# SCHEMATICS.net
KiCad netlist of a schematic drawn in Altium Designer
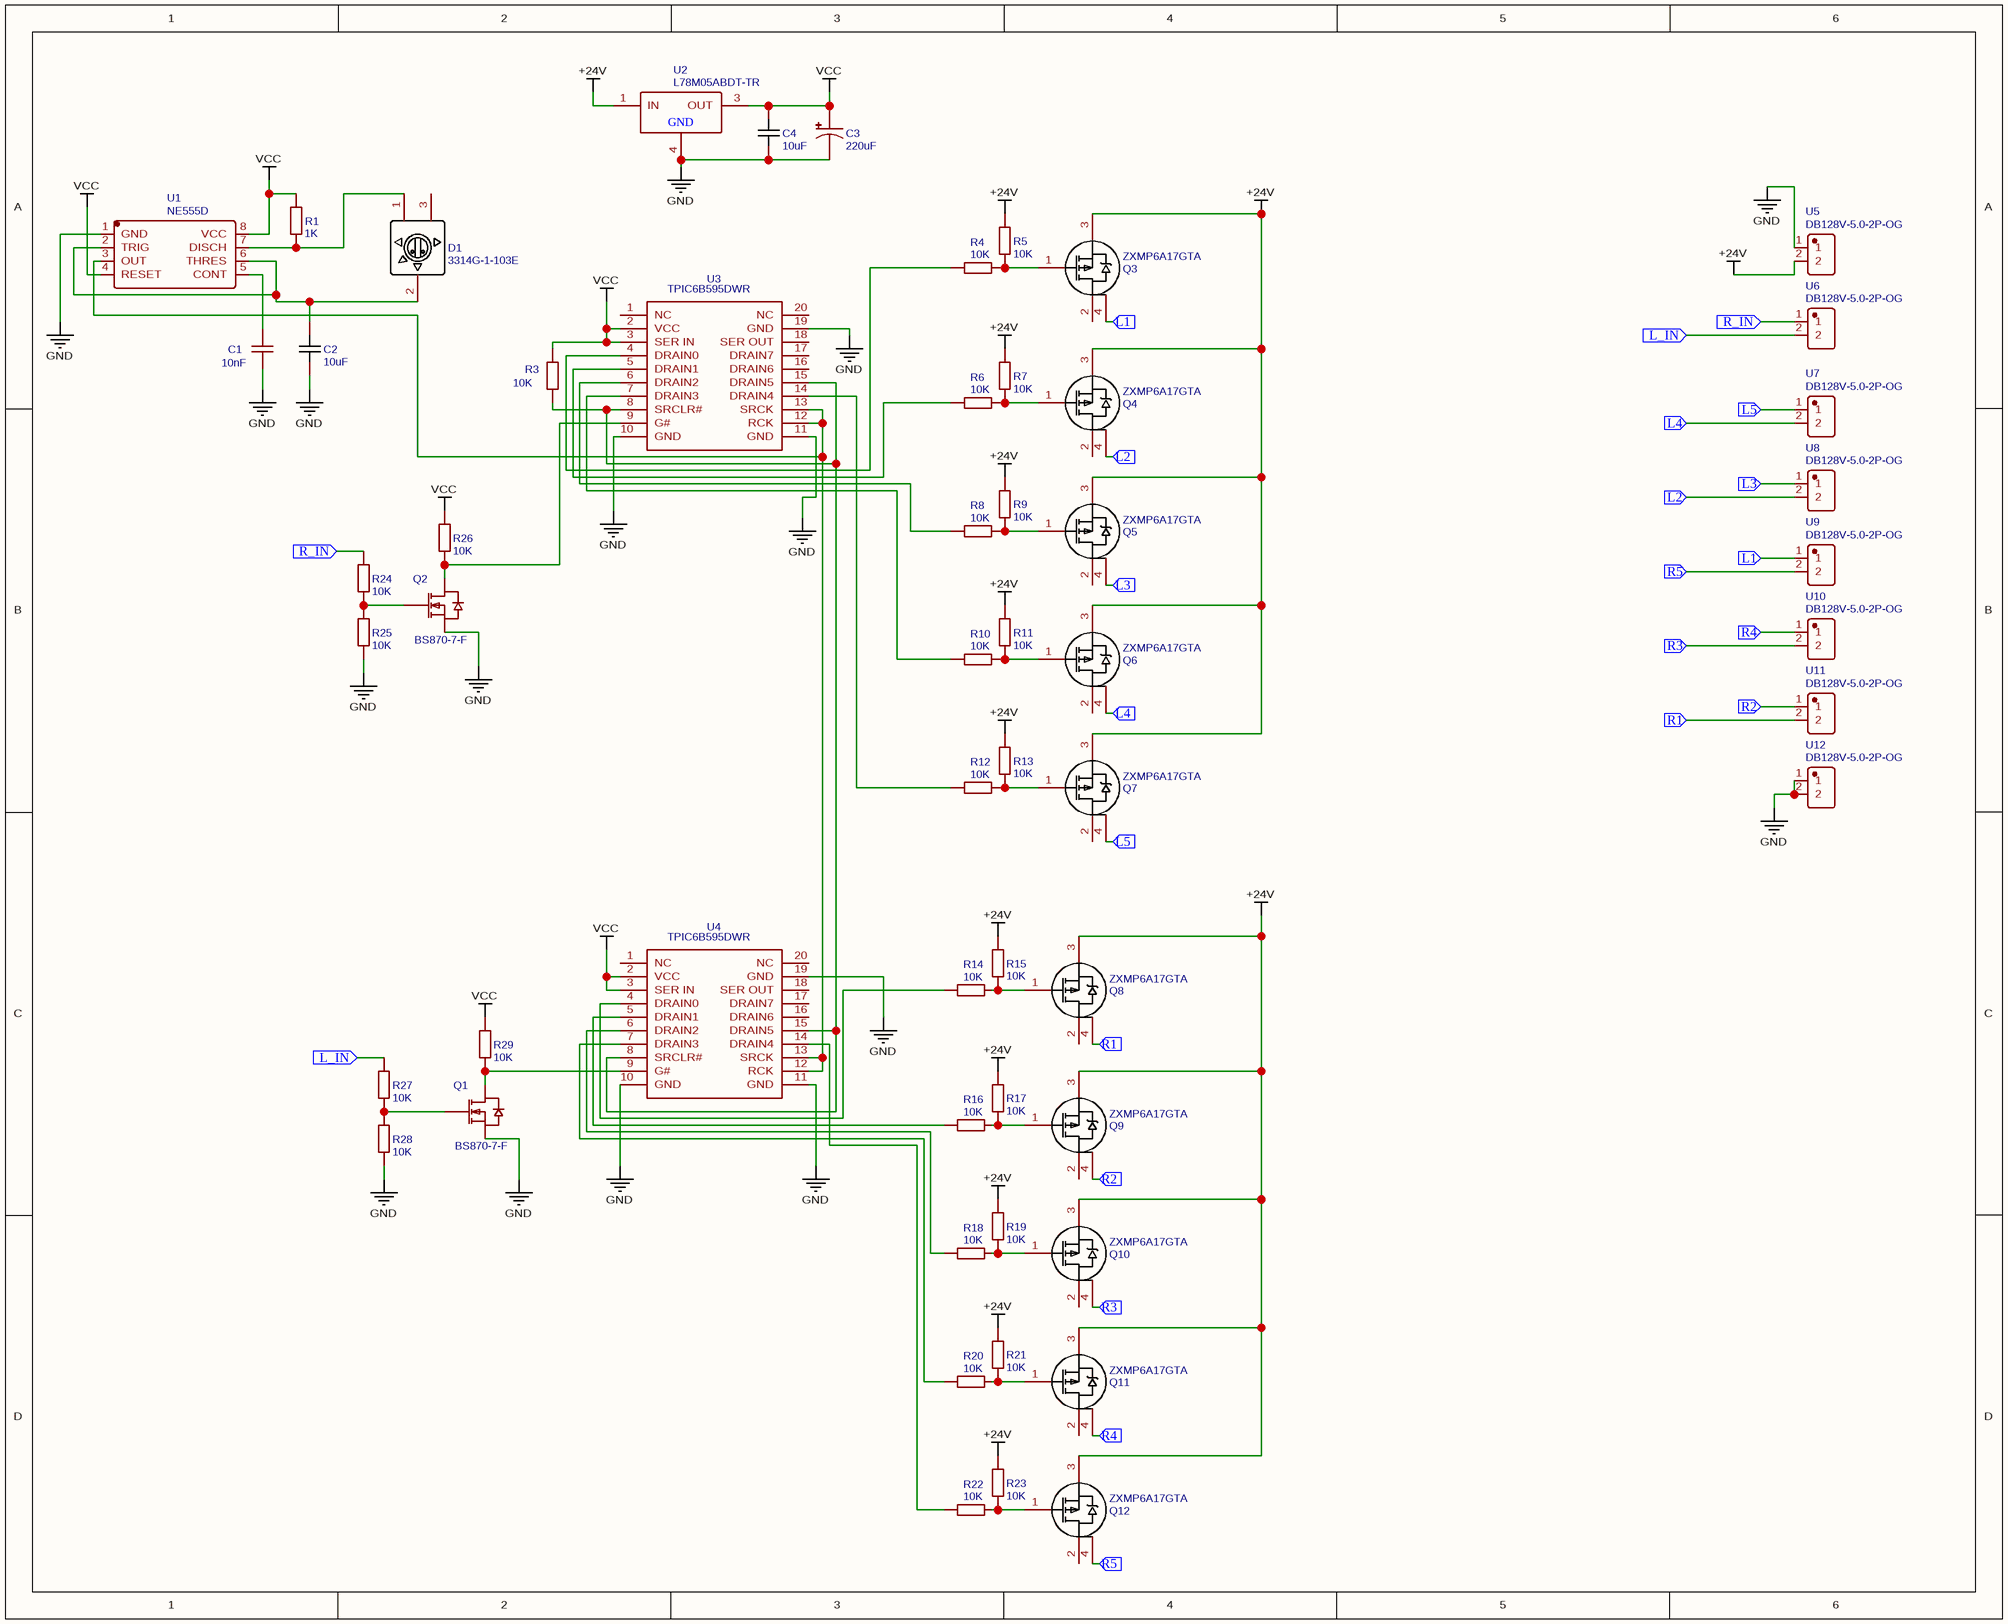
[diagram p0: SCHEMATICS.schdoc]

(export (version "E")
  (design (tool "Eeschema 10.0.6"))
  (components
    (comp (ref "C1")
      (value "10nF")
      (fields
        (field (name "BOM_MANUFACTURER PART") "CL10B103KC8NNNC")
        (field (name "BOM_SUPPLIER PART") "C84709")
        (field (name "CONTRIBUTOR") "LCSC")
      )
      (libsource (lib "altium-import") (part "root_3_10nF_"))
    )
    (comp (ref "C2")
      (value "10uF")
      (fields
        (field (name "BOM_MANUFACTURER PART") "CL10A106KP8NNNC")
        (field (name "BOM_SUPPLIER PART") "C19702")
      )
      (libsource (lib "altium-import") (part "root_3_10uF_"))
    )
    (comp (ref "C3")
      (value "220uF")
      (fields
        (field (name "BOM_SUPPLIER PART") "C250080")
        (field (name "BOM_MANUFACTURER PART") "OVU221M1C1010-TRO")
        (field (name "CONTRIBUTOR") "LCSC")
      )
      (libsource (lib "altium-import") (part "root_0_220uF_"))
    )
    (comp (ref "C4")
      (value "10uF")
      (fields
        (field (name "BOM_MANUFACTURER PART") "CL10A106KP8NNNC")
        (field (name "BOM_SUPPLIER PART") "C19702")
      )
      (libsource (lib "altium-import") (part "root_3_10uF_"))
    )
    (comp (ref "D1")
      (value "3314G-1-103E")
      (fields (field (name "BOM_SUPPLIER PART") "C780220") (field (name "CONTRIBUTOR") "LCSC"))
      (libsource (lib "altium-import") (part "root_2_3314G-1-103E_"))
    )
    (comp (ref "Q1")
      (value "BS870-7-F")
      (fields (field (name "BOM_SUPPLIER PART") "C216212") (field (name "CONTRIBUTOR") "LCSC"))
      (libsource (lib "altium-import") (part "root_0_BS870-7-F_"))
    )
    (comp (ref "Q2")
      (value "BS870-7-F")
      (fields (field (name "BOM_SUPPLIER PART") "C216212") (field (name "CONTRIBUTOR") "LCSC"))
      (libsource (lib "altium-import") (part "root_0_BS870-7-F_"))
    )
    (comp (ref "Q3")
      (value "ZXMP6A17GTA")
      (fields (field (name "BOM_SUPPLIER PART") "C154719") (field (name "CONTRIBUTOR") "LCSC"))
      (libsource (lib "altium-import") (part "root_0_ZXMP6A17GTA_"))
    )
    (comp (ref "Q4")
      (value "ZXMP6A17GTA")
      (fields (field (name "BOM_SUPPLIER PART") "C154719") (field (name "CONTRIBUTOR") "LCSC"))
      (libsource (lib "altium-import") (part "root_0_ZXMP6A17GTA_"))
    )
    (comp (ref "Q5")
      (value "ZXMP6A17GTA")
      (fields (field (name "BOM_SUPPLIER PART") "C154719") (field (name "CONTRIBUTOR") "LCSC"))
      (libsource (lib "altium-import") (part "root_0_ZXMP6A17GTA_"))
    )
    (comp (ref "Q6")
      (value "ZXMP6A17GTA")
      (fields (field (name "BOM_SUPPLIER PART") "C154719") (field (name "CONTRIBUTOR") "LCSC"))
      (libsource (lib "altium-import") (part "root_0_ZXMP6A17GTA_"))
    )
    (comp (ref "Q7")
      (value "ZXMP6A17GTA")
      (fields (field (name "BOM_SUPPLIER PART") "C154719") (field (name "CONTRIBUTOR") "LCSC"))
      (libsource (lib "altium-import") (part "root_0_ZXMP6A17GTA_"))
    )
    (comp (ref "Q8")
      (value "ZXMP6A17GTA")
      (fields (field (name "BOM_SUPPLIER PART") "C154719") (field (name "CONTRIBUTOR") "LCSC"))
      (libsource (lib "altium-import") (part "root_0_ZXMP6A17GTA_"))
    )
    (comp (ref "Q9")
      (value "ZXMP6A17GTA")
      (fields (field (name "BOM_SUPPLIER PART") "C154719") (field (name "CONTRIBUTOR") "LCSC"))
      (libsource (lib "altium-import") (part "root_0_ZXMP6A17GTA_"))
    )
    (comp (ref "Q10")
      (value "ZXMP6A17GTA")
      (fields (field (name "BOM_SUPPLIER PART") "C154719") (field (name "CONTRIBUTOR") "LCSC"))
      (libsource (lib "altium-import") (part "root_0_ZXMP6A17GTA_"))
    )
    (comp (ref "Q11")
      (value "ZXMP6A17GTA")
      (fields (field (name "BOM_SUPPLIER PART") "C154719") (field (name "CONTRIBUTOR") "LCSC"))
      (libsource (lib "altium-import") (part "root_0_ZXMP6A17GTA_"))
    )
    (comp (ref "Q12")
      (value "ZXMP6A17GTA")
      (fields (field (name "BOM_SUPPLIER PART") "C154719") (field (name "CONTRIBUTOR") "LCSC"))
      (libsource (lib "altium-import") (part "root_0_ZXMP6A17GTA_"))
    )
    (comp (ref "R1")
      (value "1K")
      (fields
        (field (name "BOM_MANUFACTURER PART") "0603WAF1001T5E")
        (field (name "BOM_SUPPLIER PART") "C21190")
      )
      (libsource (lib "altium-import") (part "root_3_1K_"))
    )
    (comp (ref "R3")
      (value "10K")
      (fields
        (field (name "BOM_MANUFACTURER PART") "0603WAF1002T5E")
        (field (name "BOM_SUPPLIER PART") "C25804")
      )
      (libsource (lib "altium-import") (part "root_3_10K_"))
    )
    (comp (ref "R4")
      (value "10K")
      (fields
        (field (name "BOM_MANUFACTURER PART") "0603WAF1002T5E")
        (field (name "BOM_SUPPLIER PART") "C25804")
      )
      (libsource (lib "altium-import") (part "root_0_10K_"))
    )
    (comp (ref "R5")
      (value "10K")
      (fields
        (field (name "BOM_MANUFACTURER PART") "0603WAF1002T5E")
        (field (name "BOM_SUPPLIER PART") "C25804")
      )
      (libsource (lib "altium-import") (part "root_3_10K_"))
    )
    (comp (ref "R6")
      (value "10K")
      (fields
        (field (name "BOM_MANUFACTURER PART") "0603WAF1002T5E")
        (field (name "BOM_SUPPLIER PART") "C25804")
      )
      (libsource (lib "altium-import") (part "root_0_10K_"))
    )
    (comp (ref "R7")
      (value "10K")
      (fields
        (field (name "BOM_MANUFACTURER PART") "0603WAF1002T5E")
        (field (name "BOM_SUPPLIER PART") "C25804")
      )
      (libsource (lib "altium-import") (part "root_3_10K_"))
    )
    (comp (ref "R8")
      (value "10K")
      (fields
        (field (name "BOM_MANUFACTURER PART") "0603WAF1002T5E")
        (field (name "BOM_SUPPLIER PART") "C25804")
      )
      (libsource (lib "altium-import") (part "root_0_10K_"))
    )
    (comp (ref "R9")
      (value "10K")
      (fields
        (field (name "BOM_MANUFACTURER PART") "0603WAF1002T5E")
        (field (name "BOM_SUPPLIER PART") "C25804")
      )
      (libsource (lib "altium-import") (part "root_3_10K_"))
    )
    (comp (ref "R10")
      (value "10K")
      (fields
        (field (name "BOM_MANUFACTURER PART") "0603WAF1002T5E")
        (field (name "BOM_SUPPLIER PART") "C25804")
      )
      (libsource (lib "altium-import") (part "root_0_10K_"))
    )
    (comp (ref "R11")
      (value "10K")
      (fields
        (field (name "BOM_MANUFACTURER PART") "0603WAF1002T5E")
        (field (name "BOM_SUPPLIER PART") "C25804")
      )
      (libsource (lib "altium-import") (part "root_3_10K_"))
    )
    (comp (ref "R12")
      (value "10K")
      (fields
        (field (name "BOM_MANUFACTURER PART") "0603WAF1002T5E")
        (field (name "BOM_SUPPLIER PART") "C25804")
      )
      (libsource (lib "altium-import") (part "root_0_10K_"))
    )
    (comp (ref "R13")
      (value "10K")
      (fields
        (field (name "BOM_MANUFACTURER PART") "0603WAF1002T5E")
        (field (name "BOM_SUPPLIER PART") "C25804")
      )
      (libsource (lib "altium-import") (part "root_3_10K_"))
    )
    (comp (ref "R14")
      (value "10K")
      (fields
        (field (name "BOM_MANUFACTURER PART") "0603WAF1002T5E")
        (field (name "BOM_SUPPLIER PART") "C25804")
      )
      (libsource (lib "altium-import") (part "root_0_10K_"))
    )
    (comp (ref "R15")
      (value "10K")
      (fields
        (field (name "BOM_MANUFACTURER PART") "0603WAF1002T5E")
        (field (name "BOM_SUPPLIER PART") "C25804")
      )
      (libsource (lib "altium-import") (part "root_3_10K_"))
    )
    (comp (ref "R16")
      (value "10K")
      (fields
        (field (name "BOM_MANUFACTURER PART") "0603WAF1002T5E")
        (field (name "BOM_SUPPLIER PART") "C25804")
      )
      (libsource (lib "altium-import") (part "root_0_10K_"))
    )
    (comp (ref "R17")
      (value "10K")
      (fields
        (field (name "BOM_MANUFACTURER PART") "0603WAF1002T5E")
        (field (name "BOM_SUPPLIER PART") "C25804")
      )
      (libsource (lib "altium-import") (part "root_3_10K_"))
    )
    (comp (ref "R18")
      (value "10K")
      (fields
        (field (name "BOM_MANUFACTURER PART") "0603WAF1002T5E")
        (field (name "BOM_SUPPLIER PART") "C25804")
      )
      (libsource (lib "altium-import") (part "root_0_10K_"))
    )
    (comp (ref "R19")
      (value "10K")
      (fields
        (field (name "BOM_MANUFACTURER PART") "0603WAF1002T5E")
        (field (name "BOM_SUPPLIER PART") "C25804")
      )
      (libsource (lib "altium-import") (part "root_3_10K_"))
    )
    (comp (ref "R20")
      (value "10K")
      (fields
        (field (name "BOM_MANUFACTURER PART") "0603WAF1002T5E")
        (field (name "BOM_SUPPLIER PART") "C25804")
      )
      (libsource (lib "altium-import") (part "root_0_10K_"))
    )
    (comp (ref "R21")
      (value "10K")
      (fields
        (field (name "BOM_MANUFACTURER PART") "0603WAF1002T5E")
        (field (name "BOM_SUPPLIER PART") "C25804")
      )
      (libsource (lib "altium-import") (part "root_3_10K_"))
    )
    (comp (ref "R22")
      (value "10K")
      (fields
        (field (name "BOM_MANUFACTURER PART") "0603WAF1002T5E")
        (field (name "BOM_SUPPLIER PART") "C25804")
      )
      (libsource (lib "altium-import") (part "root_0_10K_"))
    )
    (comp (ref "R23")
      (value "10K")
      (fields
        (field (name "BOM_MANUFACTURER PART") "0603WAF1002T5E")
        (field (name "BOM_SUPPLIER PART") "C25804")
      )
      (libsource (lib "altium-import") (part "root_3_10K_"))
    )
    (comp (ref "R24")
      (value "10K")
      (fields
        (field (name "BOM_MANUFACTURER PART") "0603WAF1002T5E")
        (field (name "BOM_SUPPLIER PART") "C25804")
      )
      (libsource (lib "altium-import") (part "root_1_10K_"))
    )
    (comp (ref "R25")
      (value "10K")
      (fields
        (field (name "BOM_MANUFACTURER PART") "0603WAF1002T5E")
        (field (name "BOM_SUPPLIER PART") "C25804")
      )
      (libsource (lib "altium-import") (part "root_1_10K_"))
    )
    (comp (ref "R26")
      (value "10K")
      (fields
        (field (name "BOM_MANUFACTURER PART") "0603WAF1002T5E")
        (field (name "BOM_SUPPLIER PART") "C25804")
      )
      (libsource (lib "altium-import") (part "root_1_10K_"))
    )
    (comp (ref "R27")
      (value "10K")
      (fields
        (field (name "BOM_MANUFACTURER PART") "0603WAF1002T5E")
        (field (name "BOM_SUPPLIER PART") "C25804")
      )
      (libsource (lib "altium-import") (part "root_1_10K_"))
    )
    (comp (ref "R28")
      (value "10K")
      (fields
        (field (name "BOM_MANUFACTURER PART") "0603WAF1002T5E")
        (field (name "BOM_SUPPLIER PART") "C25804")
      )
      (libsource (lib "altium-import") (part "root_1_10K_"))
    )
    (comp (ref "R29")
      (value "10K")
      (fields
        (field (name "BOM_MANUFACTURER PART") "0603WAF1002T5E")
        (field (name "BOM_SUPPLIER PART") "C25804")
      )
      (libsource (lib "altium-import") (part "root_1_10K_"))
    )
    (comp (ref "U1")
      (value "NE555D")
      (fields (field (name "BOM_SUPPLIER PART") "C234230") (field (name "CONTRIBUTOR") "LCSC"))
      (libsource (lib "altium-import") (part "root_0_NE555D_"))
    )
    (comp (ref "U2")
      (value "L78M05ABDT-TR")
      (fields (field (name "BOM_SUPPLIER PART") "C58069"))
      (libsource (lib "altium-import") (part "root_0_L78M05ABDT-TR_"))
    )
    (comp (ref "U3")
      (value "TPIC6B595DWR")
      (fields (field (name "BOM_SUPPLIER PART") "C7094"))
      (libsource (lib "altium-import") (part "root_0_TPIC6B595DWR_"))
    )
    (comp (ref "U4")
      (value "TPIC6B595DWR")
      (fields (field (name "BOM_SUPPLIER PART") "C7094"))
      (libsource (lib "altium-import") (part "root_0_TPIC6B595DWR_"))
    )
    (comp (ref "U5")
      (value "DB128V-5.0-2P-OG")
      (fields (field (name "BOM_SUPPLIER PART") "C424694") (field (name "CONTRIBUTOR") "LCSC"))
      (libsource (lib "altium-import") (part "root_0_DB128V-5.0-2P-OG_"))
    )
    (comp (ref "U6")
      (value "DB128V-5.0-2P-OG")
      (fields (field (name "BOM_SUPPLIER PART") "C424694") (field (name "CONTRIBUTOR") "LCSC"))
      (libsource (lib "altium-import") (part "root_0_DB128V-5.0-2P-OG_"))
    )
    (comp (ref "U7")
      (value "DB128V-5.0-2P-OG")
      (fields (field (name "BOM_SUPPLIER PART") "C424694") (field (name "CONTRIBUTOR") "LCSC"))
      (libsource (lib "altium-import") (part "root_0_DB128V-5.0-2P-OG_"))
    )
    (comp (ref "U8")
      (value "DB128V-5.0-2P-OG")
      (fields (field (name "BOM_SUPPLIER PART") "C424694") (field (name "CONTRIBUTOR") "LCSC"))
      (libsource (lib "altium-import") (part "root_0_DB128V-5.0-2P-OG_"))
    )
    (comp (ref "U9")
      (value "DB128V-5.0-2P-OG")
      (fields (field (name "BOM_SUPPLIER PART") "C424694") (field (name "CONTRIBUTOR") "LCSC"))
      (libsource (lib "altium-import") (part "root_0_DB128V-5.0-2P-OG_"))
    )
    (comp (ref "U10")
      (value "DB128V-5.0-2P-OG")
      (fields (field (name "BOM_SUPPLIER PART") "C424694") (field (name "CONTRIBUTOR") "LCSC"))
      (libsource (lib "altium-import") (part "root_0_DB128V-5.0-2P-OG_"))
    )
    (comp (ref "U11")
      (value "DB128V-5.0-2P-OG")
      (fields (field (name "BOM_SUPPLIER PART") "C424694") (field (name "CONTRIBUTOR") "LCSC"))
      (libsource (lib "altium-import") (part "root_0_DB128V-5.0-2P-OG_"))
    )
    (comp (ref "U12")
      (value "DB128V-5.0-2P-OG")
      (fields (field (name "BOM_SUPPLIER PART") "C424694") (field (name "CONTRIBUTOR") "LCSC"))
      (libsource (lib "altium-import") (part "root_0_DB128V-5.0-2P-OG_"))
    )
  )
  (nets
    (net (code "1") (name "+24V") (class "Default")
      (node (ref "Q10") (pin "3") (pinfunction "S_3") (pintype "passive"))
      (node (ref "Q11") (pin "3") (pinfunction "S_3") (pintype "passive"))
      (node (ref "Q12") (pin "3") (pinfunction "S_3") (pintype "passive"))
      (node (ref "Q3") (pin "3") (pinfunction "S_3") (pintype "passive"))
      (node (ref "Q4") (pin "3") (pinfunction "S_3") (pintype "passive"))
      (node (ref "Q5") (pin "3") (pinfunction "S_3") (pintype "passive"))
      (node (ref "Q6") (pin "3") (pinfunction "S_3") (pintype "passive"))
      (node (ref "Q7") (pin "3") (pinfunction "S_3") (pintype "passive"))
      (node (ref "Q8") (pin "3") (pinfunction "S_3") (pintype "passive"))
      (node (ref "Q9") (pin "3") (pinfunction "S_3") (pintype "passive"))
      (node (ref "R11") (pin "1") (pinfunction "1_1") (pintype "passive"))
      (node (ref "R13") (pin "1") (pinfunction "1_1") (pintype "passive"))
      (node (ref "R15") (pin "1") (pinfunction "1_1") (pintype "passive"))
      (node (ref "R17") (pin "1") (pinfunction "1_1") (pintype "passive"))
      (node (ref "R19") (pin "1") (pinfunction "1_1") (pintype "passive"))
      (node (ref "R21") (pin "1") (pinfunction "1_1") (pintype "passive"))
      (node (ref "R23") (pin "1") (pinfunction "1_1") (pintype "passive"))
      (node (ref "R5") (pin "1") (pinfunction "1_1") (pintype "passive"))
      (node (ref "R7") (pin "1") (pinfunction "1_1") (pintype "passive"))
      (node (ref "R9") (pin "1") (pinfunction "1_1") (pintype "passive"))
      (node (ref "U2") (pin "1") (pinfunction "IN_1") (pintype "passive"))
      (node (ref "U5") (pin "2") (pinfunction "2_2") (pintype "passive"))
    )
    (net (code "2") (name "/L1") (class "Default")
      (node (ref "Q3") (pin "4") (pinfunction "D_4") (pintype "passive"))
      (node (ref "U9") (pin "1") (pinfunction "1_1") (pintype "passive"))
    )
    (net (code "3") (name "/L2") (class "Default")
      (node (ref "Q4") (pin "4") (pinfunction "D_4") (pintype "passive"))
      (node (ref "U8") (pin "2") (pinfunction "2_2") (pintype "passive"))
    )
    (net (code "4") (name "/L3") (class "Default")
      (node (ref "Q5") (pin "4") (pinfunction "D_4") (pintype "passive"))
      (node (ref "U8") (pin "1") (pinfunction "1_1") (pintype "passive"))
    )
    (net (code "5") (name "/L4") (class "Default")
      (node (ref "Q6") (pin "4") (pinfunction "D_4") (pintype "passive"))
      (node (ref "U7") (pin "2") (pinfunction "2_2") (pintype "passive"))
    )
    (net (code "6") (name "/L5") (class "Default")
      (node (ref "Q7") (pin "4") (pinfunction "D_4") (pintype "passive"))
      (node (ref "U7") (pin "1") (pinfunction "1_1") (pintype "passive"))
    )
    (net (code "7") (name "/L_IN") (class "Default")
      (node (ref "R27") (pin "2") (pinfunction "2_2") (pintype "passive"))
      (node (ref "U6") (pin "2") (pinfunction "2_2") (pintype "passive"))
    )
    (net (code "8") (name "/R1") (class "Default")
      (node (ref "Q8") (pin "4") (pinfunction "D_4") (pintype "passive"))
      (node (ref "U11") (pin "2") (pinfunction "2_2") (pintype "passive"))
    )
    (net (code "9") (name "/R2") (class "Default")
      (node (ref "Q9") (pin "4") (pinfunction "D_4") (pintype "passive"))
      (node (ref "U11") (pin "1") (pinfunction "1_1") (pintype "passive"))
    )
    (net (code "10") (name "/R3") (class "Default")
      (node (ref "Q10") (pin "4") (pinfunction "D_4") (pintype "passive"))
      (node (ref "U10") (pin "2") (pinfunction "2_2") (pintype "passive"))
    )
    (net (code "11") (name "/R4") (class "Default")
      (node (ref "Q11") (pin "4") (pinfunction "D_4") (pintype "passive"))
      (node (ref "U10") (pin "1") (pinfunction "1_1") (pintype "passive"))
    )
    (net (code "12") (name "/R5") (class "Default")
      (node (ref "Q12") (pin "4") (pinfunction "D_4") (pintype "passive"))
      (node (ref "U9") (pin "2") (pinfunction "2_2") (pintype "passive"))
    )
    (net (code "13") (name "/R_IN") (class "Default")
      (node (ref "R24") (pin "2") (pinfunction "2_2") (pintype "passive"))
      (node (ref "U6") (pin "1") (pinfunction "1_1") (pintype "passive"))
    )
    (net (code "14") (name "GND") (class "Default")
      (node (ref "C1") (pin "2") (pinfunction "2_2") (pintype "passive"))
      (node (ref "C2") (pin "2") (pinfunction "2_2") (pintype "passive"))
      (node (ref "C3") (pin "2") (pinfunction "2_2") (pintype "passive"))
      (node (ref "C4") (pin "2") (pinfunction "2_2") (pintype "passive"))
      (node (ref "Q1") (pin "2") (pinfunction "S_2") (pintype "passive"))
      (node (ref "Q2") (pin "2") (pinfunction "S_2") (pintype "passive"))
      (node (ref "R25") (pin "1") (pinfunction "1_1") (pintype "passive"))
      (node (ref "R28") (pin "1") (pinfunction "1_1") (pintype "passive"))
      (node (ref "U1") (pin "1") (pinfunction "GND_1") (pintype "passive"))
      (node (ref "U12") (pin "1") (pinfunction "1_1") (pintype "passive"))
      (node (ref "U12") (pin "2") (pinfunction "2_2") (pintype "passive"))
      (node (ref "U2") (pin "4") (pinfunction "GND_4") (pintype "passive"))
      (node (ref "U3") (pin "10") (pinfunction "GND_10") (pintype "passive"))
      (node (ref "U3") (pin "11") (pinfunction "GND_11") (pintype "passive"))
      (node (ref "U3") (pin "19") (pinfunction "GND_19") (pintype "passive"))
      (node (ref "U4") (pin "10") (pinfunction "GND_10") (pintype "passive"))
      (node (ref "U4") (pin "11") (pinfunction "GND_11") (pintype "passive"))
      (node (ref "U4") (pin "19") (pinfunction "GND_19") (pintype "passive"))
      (node (ref "U5") (pin "1") (pinfunction "1_1") (pintype "passive"))
    )
    (net (code "15") (name "Net-(Q1-D)") (class "Default")
      (node (ref "Q1") (pin "3") (pinfunction "D_3") (pintype "passive"))
      (node (ref "R29") (pin "1") (pinfunction "1_1") (pintype "passive"))
      (node (ref "U4") (pin "9") (pinfunction "G#_9") (pintype "passive"))
    )
    (net (code "16") (name "Net-(Q1-G)") (class "Default")
      (node (ref "Q1") (pin "1") (pinfunction "G_1") (pintype "passive"))
      (node (ref "R27") (pin "1") (pinfunction "1_1") (pintype "passive"))
      (node (ref "R28") (pin "2") (pinfunction "2_2") (pintype "passive"))
    )
    (net (code "17") (name "Net-(Q2-D)") (class "Default")
      (node (ref "Q2") (pin "3") (pinfunction "D_3") (pintype "passive"))
      (node (ref "R26") (pin "1") (pinfunction "1_1") (pintype "passive"))
      (node (ref "U3") (pin "9") (pinfunction "G#_9") (pintype "passive"))
    )
    (net (code "18") (name "Net-(Q2-G)") (class "Default")
      (node (ref "Q2") (pin "1") (pinfunction "G_1") (pintype "passive"))
      (node (ref "R24") (pin "1") (pinfunction "1_1") (pintype "passive"))
      (node (ref "R25") (pin "2") (pinfunction "2_2") (pintype "passive"))
    )
    (net (code "19") (name "Net-(Q3-G)") (class "Default")
      (node (ref "Q3") (pin "1") (pinfunction "G_1") (pintype "passive"))
      (node (ref "R4") (pin "2") (pinfunction "2_2") (pintype "passive"))
      (node (ref "R5") (pin "2") (pinfunction "2_2") (pintype "passive"))
    )
    (net (code "20") (name "Net-(Q4-G)") (class "Default")
      (node (ref "Q4") (pin "1") (pinfunction "G_1") (pintype "passive"))
      (node (ref "R6") (pin "2") (pinfunction "2_2") (pintype "passive"))
      (node (ref "R7") (pin "2") (pinfunction "2_2") (pintype "passive"))
    )
    (net (code "21") (name "Net-(Q5-G)") (class "Default")
      (node (ref "Q5") (pin "1") (pinfunction "G_1") (pintype "passive"))
      (node (ref "R8") (pin "2") (pinfunction "2_2") (pintype "passive"))
      (node (ref "R9") (pin "2") (pinfunction "2_2") (pintype "passive"))
    )
    (net (code "22") (name "Net-(Q6-G)") (class "Default")
      (node (ref "Q6") (pin "1") (pinfunction "G_1") (pintype "passive"))
      (node (ref "R10") (pin "2") (pinfunction "2_2") (pintype "passive"))
      (node (ref "R11") (pin "2") (pinfunction "2_2") (pintype "passive"))
    )
    (net (code "23") (name "Net-(Q7-G)") (class "Default")
      (node (ref "Q7") (pin "1") (pinfunction "G_1") (pintype "passive"))
      (node (ref "R12") (pin "2") (pinfunction "2_2") (pintype "passive"))
      (node (ref "R13") (pin "2") (pinfunction "2_2") (pintype "passive"))
    )
    (net (code "24") (name "Net-(Q8-G)") (class "Default")
      (node (ref "Q8") (pin "1") (pinfunction "G_1") (pintype "passive"))
      (node (ref "R14") (pin "2") (pinfunction "2_2") (pintype "passive"))
      (node (ref "R15") (pin "2") (pinfunction "2_2") (pintype "passive"))
    )
    (net (code "25") (name "Net-(Q9-G)") (class "Default")
      (node (ref "Q9") (pin "1") (pinfunction "G_1") (pintype "passive"))
      (node (ref "R16") (pin "2") (pinfunction "2_2") (pintype "passive"))
      (node (ref "R17") (pin "2") (pinfunction "2_2") (pintype "passive"))
    )
    (net (code "26") (name "Net-(Q10-G)") (class "Default")
      (node (ref "Q10") (pin "1") (pinfunction "G_1") (pintype "passive"))
      (node (ref "R18") (pin "2") (pinfunction "2_2") (pintype "passive"))
      (node (ref "R19") (pin "2") (pinfunction "2_2") (pintype "passive"))
    )
    (net (code "27") (name "Net-(Q11-G)") (class "Default")
      (node (ref "Q11") (pin "1") (pinfunction "G_1") (pintype "passive"))
      (node (ref "R20") (pin "2") (pinfunction "2_2") (pintype "passive"))
      (node (ref "R21") (pin "2") (pinfunction "2_2") (pintype "passive"))
    )
    (net (code "28") (name "Net-(Q12-G)") (class "Default")
      (node (ref "Q12") (pin "1") (pinfunction "G_1") (pintype "passive"))
      (node (ref "R22") (pin "2") (pinfunction "2_2") (pintype "passive"))
      (node (ref "R23") (pin "2") (pinfunction "2_2") (pintype "passive"))
    )
    (net (code "29") (name "Net-(U1-CONT)") (class "Default")
      (node (ref "C1") (pin "1") (pinfunction "1_1") (pintype "passive"))
      (node (ref "U1") (pin "5") (pinfunction "CONT_5") (pintype "passive"))
    )
    (net (code "30") (name "Net-(U1-DISCH)") (class "Default")
      (node (ref "D1") (pin "1") (pinfunction "1_1") (pintype "passive"))
      (node (ref "R1") (pin "1") (pinfunction "1_1") (pintype "passive"))
      (node (ref "U1") (pin "7") (pinfunction "DISCH_7") (pintype "passive"))
    )
    (net (code "31") (name "Net-(U1-OUT)") (class "Default")
      (node (ref "U1") (pin "3") (pinfunction "OUT_3") (pintype "passive"))
      (node (ref "U3") (pin "12") (pinfunction "RCK_12") (pintype "passive"))
      (node (ref "U3") (pin "13") (pinfunction "SRCK_13") (pintype "passive"))
      (node (ref "U4") (pin "12") (pinfunction "RCK_12") (pintype "passive"))
      (node (ref "U4") (pin "13") (pinfunction "SRCK_13") (pintype "passive"))
    )
    (net (code "32") (name "Net-(U1-THRES)") (class "Default")
      (node (ref "C2") (pin "1") (pinfunction "1_1") (pintype "passive"))
      (node (ref "D1") (pin "2") (pinfunction "2_2") (pintype "passive"))
      (node (ref "U1") (pin "2") (pinfunction "TRIG_2") (pintype "passive"))
      (node (ref "U1") (pin "6") (pinfunction "THRES_6") (pintype "passive"))
    )
    (net (code "33") (name "Net-(U3-DRAIN0)") (class "Default")
      (node (ref "R4") (pin "1") (pinfunction "1_1") (pintype "passive"))
      (node (ref "U3") (pin "4") (pinfunction "DRAIN0_4") (pintype "passive"))
    )
    (net (code "34") (name "Net-(U3-DRAIN1)") (class "Default")
      (node (ref "R6") (pin "1") (pinfunction "1_1") (pintype "passive"))
      (node (ref "U3") (pin "5") (pinfunction "DRAIN1_5") (pintype "passive"))
    )
    (net (code "35") (name "Net-(U3-DRAIN2)") (class "Default")
      (node (ref "R8") (pin "1") (pinfunction "1_1") (pintype "passive"))
      (node (ref "U3") (pin "6") (pinfunction "DRAIN2_6") (pintype "passive"))
    )
    (net (code "36") (name "Net-(U3-DRAIN3)") (class "Default")
      (node (ref "R10") (pin "1") (pinfunction "1_1") (pintype "passive"))
      (node (ref "U3") (pin "7") (pinfunction "DRAIN3_7") (pintype "passive"))
    )
    (net (code "37") (name "Net-(U3-DRAIN4)") (class "Default")
      (node (ref "R12") (pin "1") (pinfunction "1_1") (pintype "passive"))
      (node (ref "U3") (pin "14") (pinfunction "DRAIN4_14") (pintype "passive"))
    )
    (net (code "38") (name "Net-(U3-DRAIN5)") (class "Default")
      (node (ref "R3") (pin "2") (pinfunction "2_2") (pintype "passive"))
      (node (ref "U3") (pin "15") (pinfunction "DRAIN5_15") (pintype "passive"))
      (node (ref "U3") (pin "8") (pinfunction "SRCLR#_8") (pintype "passive"))
      (node (ref "U4") (pin "15") (pinfunction "DRAIN5_15") (pintype "passive"))
      (node (ref "U4") (pin "8") (pinfunction "SRCLR#_8") (pintype "passive"))
    )
    (net (code "39") (name "Net-(U4-DRAIN0)") (class "Default")
      (node (ref "R14") (pin "1") (pinfunction "1_1") (pintype "passive"))
      (node (ref "U4") (pin "4") (pinfunction "DRAIN0_4") (pintype "passive"))
    )
    (net (code "40") (name "Net-(U4-DRAIN1)") (class "Default")
      (node (ref "R16") (pin "1") (pinfunction "1_1") (pintype "passive"))
      (node (ref "U4") (pin "5") (pinfunction "DRAIN1_5") (pintype "passive"))
    )
    (net (code "41") (name "Net-(U4-DRAIN2)") (class "Default")
      (node (ref "R18") (pin "1") (pinfunction "1_1") (pintype "passive"))
      (node (ref "U4") (pin "6") (pinfunction "DRAIN2_6") (pintype "passive"))
    )
    (net (code "42") (name "Net-(U4-DRAIN3)") (class "Default")
      (node (ref "R20") (pin "1") (pinfunction "1_1") (pintype "passive"))
      (node (ref "U4") (pin "7") (pinfunction "DRAIN3_7") (pintype "passive"))
    )
    (net (code "43") (name "Net-(U4-DRAIN4)") (class "Default")
      (node (ref "R22") (pin "1") (pinfunction "1_1") (pintype "passive"))
      (node (ref "U4") (pin "14") (pinfunction "DRAIN4_14") (pintype "passive"))
    )
    (net (code "44") (name "VCC") (class "Default")
      (node (ref "C3") (pin "1") (pinfunction "1_1") (pintype "passive"))
      (node (ref "C4") (pin "1") (pinfunction "1_1") (pintype "passive"))
      (node (ref "R1") (pin "2") (pinfunction "2_2") (pintype "passive"))
      (node (ref "R26") (pin "2") (pinfunction "2_2") (pintype "passive"))
      (node (ref "R29") (pin "2") (pinfunction "2_2") (pintype "passive"))
      (node (ref "R3") (pin "1") (pinfunction "1_1") (pintype "passive"))
      (node (ref "U1") (pin "4") (pinfunction "RESET_4") (pintype "passive"))
      (node (ref "U1") (pin "8") (pinfunction "VCC_8") (pintype "passive"))
      (node (ref "U2") (pin "3") (pinfunction "OUT_3") (pintype "passive"))
      (node (ref "U3") (pin "2") (pinfunction "VCC_2") (pintype "passive"))
      (node (ref "U3") (pin "3") (pinfunction "SER_IN_3") (pintype "passive"))
      (node (ref "U4") (pin "2") (pinfunction "VCC_2") (pintype "passive"))
      (node (ref "U4") (pin "3") (pinfunction "SER_IN_3") (pintype "passive"))
    )
    (net (code "45") (name "unconnected-(D1-Pad3)") (class "Default")
      (node (ref "D1") (pin "3") (pinfunction "3_3") (pintype "passive"))
    )
    (net (code "46") (name "unconnected-(Q3-D-Pad2)") (class "Default")
      (node (ref "Q3") (pin "2") (pinfunction "D_2") (pintype "passive"))
    )
    (net (code "47") (name "unconnected-(Q4-D-Pad2)") (class "Default")
      (node (ref "Q4") (pin "2") (pinfunction "D_2") (pintype "passive"))
    )
    (net (code "48") (name "unconnected-(Q5-D-Pad2)") (class "Default")
      (node (ref "Q5") (pin "2") (pinfunction "D_2") (pintype "passive"))
    )
    (net (code "49") (name "unconnected-(Q6-D-Pad2)") (class "Default")
      (node (ref "Q6") (pin "2") (pinfunction "D_2") (pintype "passive"))
    )
    (net (code "50") (name "unconnected-(Q7-D-Pad2)") (class "Default")
      (node (ref "Q7") (pin "2") (pinfunction "D_2") (pintype "passive"))
    )
    (net (code "51") (name "unconnected-(Q8-D-Pad2)") (class "Default")
      (node (ref "Q8") (pin "2") (pinfunction "D_2") (pintype "passive"))
    )
    (net (code "52") (name "unconnected-(Q9-D-Pad2)") (class "Default")
      (node (ref "Q9") (pin "2") (pinfunction "D_2") (pintype "passive"))
    )
    (net (code "53") (name "unconnected-(Q10-D-Pad2)") (class "Default")
      (node (ref "Q10") (pin "2") (pinfunction "D_2") (pintype "passive"))
    )
    (net (code "54") (name "unconnected-(Q11-D-Pad2)") (class "Default")
      (node (ref "Q11") (pin "2") (pinfunction "D_2") (pintype "passive"))
    )
    (net (code "55") (name "unconnected-(Q12-D-Pad2)") (class "Default")
      (node (ref "Q12") (pin "2") (pinfunction "D_2") (pintype "passive"))
    )
    (net (code "56") (name "unconnected-(U3-DRAIN6-Pad16)") (class "Default")
      (node (ref "U3") (pin "16") (pinfunction "DRAIN6_16") (pintype "passive"))
    )
    (net (code "57") (name "unconnected-(U3-DRAIN7-Pad17)") (class "Default")
      (node (ref "U3") (pin "17") (pinfunction "DRAIN7_17") (pintype "passive"))
    )
    (net (code "58") (name "unconnected-(U3-NC-Pad1)") (class "Default")
      (node (ref "U3") (pin "1") (pinfunction "NC_1") (pintype "passive"))
    )
    (net (code "59") (name "unconnected-(U3-NC-Pad20)") (class "Default")
      (node (ref "U3") (pin "20") (pinfunction "NC_20") (pintype "passive"))
    )
    (net (code "60") (name "unconnected-(U3-SER_OUT-Pad18)") (class "Default")
      (node (ref "U3") (pin "18") (pinfunction "SER_OUT_18") (pintype "passive"))
    )
    (net (code "61") (name "unconnected-(U4-DRAIN6-Pad16)") (class "Default")
      (node (ref "U4") (pin "16") (pinfunction "DRAIN6_16") (pintype "passive"))
    )
    (net (code "62") (name "unconnected-(U4-DRAIN7-Pad17)") (class "Default")
      (node (ref "U4") (pin "17") (pinfunction "DRAIN7_17") (pintype "passive"))
    )
    (net (code "63") (name "unconnected-(U4-NC-Pad1)") (class "Default")
      (node (ref "U4") (pin "1") (pinfunction "NC_1") (pintype "passive"))
    )
    (net (code "64") (name "unconnected-(U4-NC-Pad20)") (class "Default")
      (node (ref "U4") (pin "20") (pinfunction "NC_20") (pintype "passive"))
    )
    (net (code "65") (name "unconnected-(U4-SER_OUT-Pad18)") (class "Default")
      (node (ref "U4") (pin "18") (pinfunction "SER_OUT_18") (pintype "passive"))
    )
  )
)
